# InvertingMixer.net
KiCad netlist of a schematic drawn in EAGLE
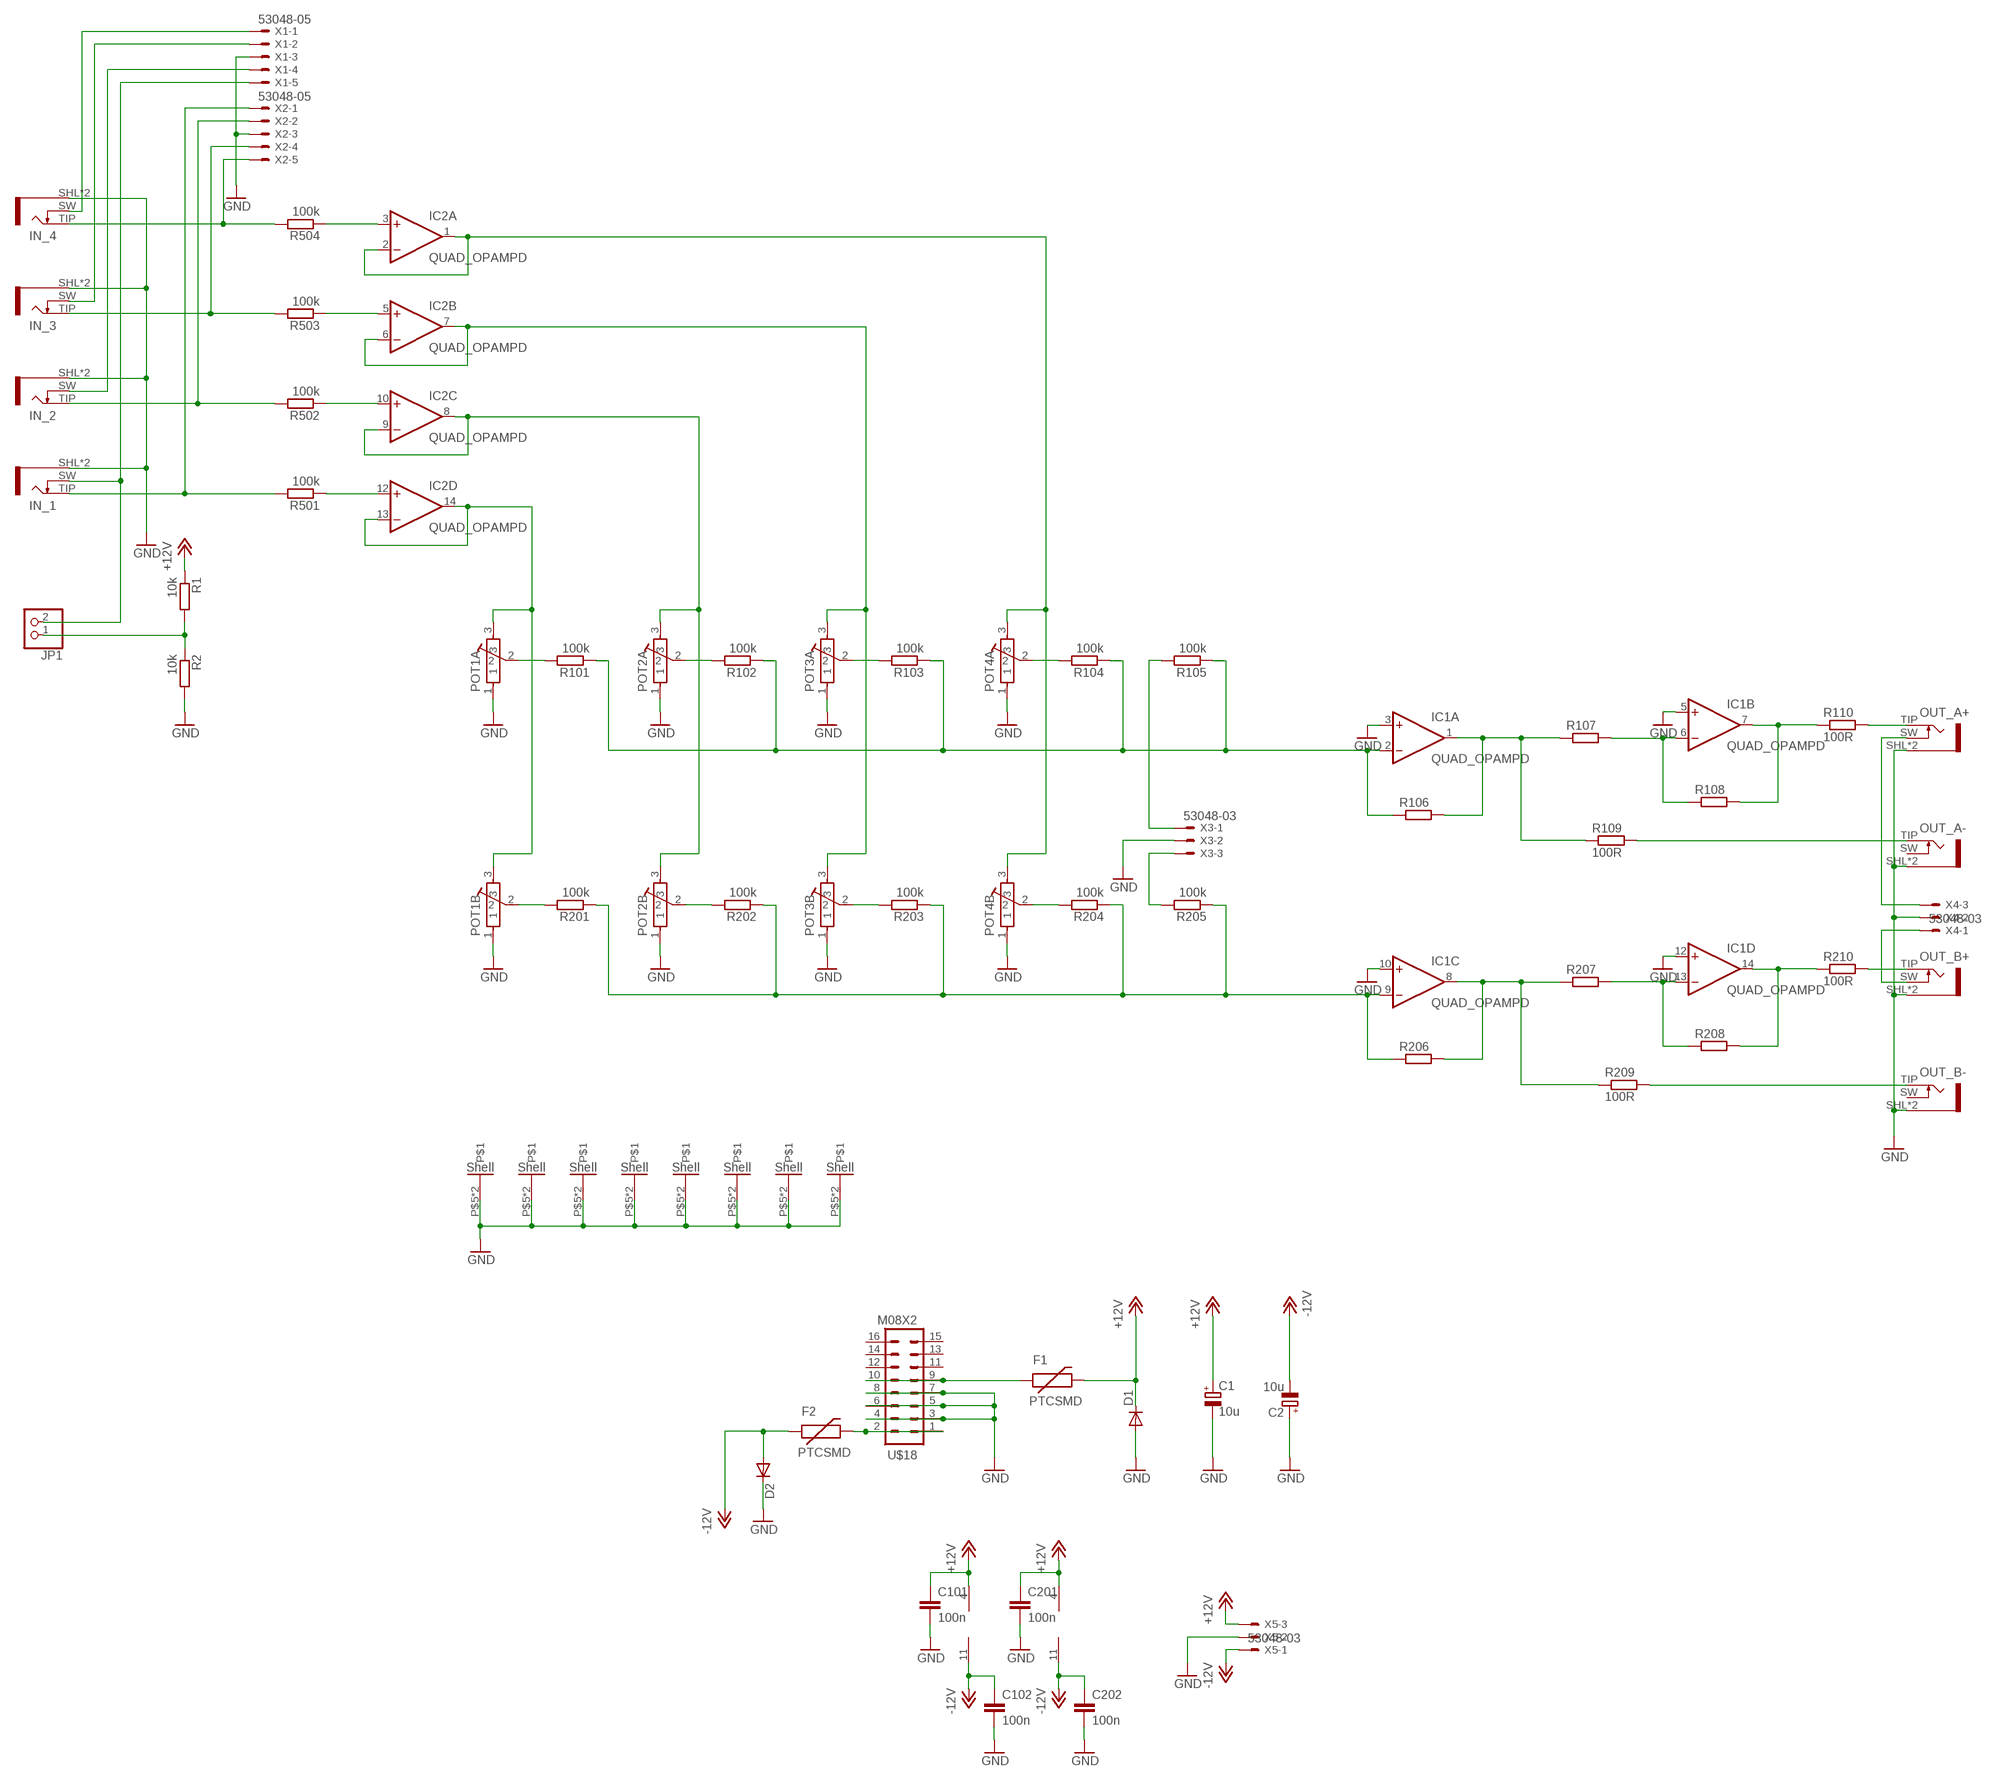
[diagram p0: schematic, sheet 1]

(export (version "E")
  (design (tool "Eeschema 10.0.6"))
  (components
    (comp (ref "C1")
      (value "10u")
      (footprint "eagle-import:PANASONIC_A")
      (libsource (lib "eagle-import") (part "CPOL-EUA"))
    )
    (comp (ref "C2")
      (value "10u")
      (footprint "eagle-import:PANASONIC_A")
      (libsource (lib "eagle-import") (part "CPOL-EUA"))
    )
    (comp (ref "C101")
      (value "100n")
      (footprint "eagle-import:C0603")
      (libsource (lib "eagle-import") (part "C-EUC0603"))
    )
    (comp (ref "C102")
      (value "100n")
      (footprint "eagle-import:C0603")
      (libsource (lib "eagle-import") (part "C-EUC0603"))
    )
    (comp (ref "C201")
      (value "100n")
      (footprint "eagle-import:C0603")
      (libsource (lib "eagle-import") (part "C-EUC0603"))
    )
    (comp (ref "C202")
      (value "100n")
      (footprint "eagle-import:C0603")
      (libsource (lib "eagle-import") (part "C-EUC0603"))
    )
    (comp (ref "D1")
      (value "DIODESMA")
      (footprint "eagle-import:SMA-DIODE")
      (libsource (lib "eagle-import") (part "DIODESMA"))
    )
    (comp (ref "D2")
      (value "DIODESMA")
      (footprint "eagle-import:SMA-DIODE")
      (libsource (lib "eagle-import") (part "DIODESMA"))
    )
    (comp (ref "F1")
      (value "PTCSMD")
      (footprint "eagle-import:PTC-1206")
      (libsource (lib "eagle-import") (part "PTCSMD"))
    )
    (comp (ref "F2")
      (value "PTCSMD")
      (footprint "eagle-import:PTC-1206")
      (libsource (lib "eagle-import") (part "PTCSMD"))
    )
    (comp (ref "IC1")
      (value "QUAD_OPAMPD")
      (footprint "eagle-import:SO14")
      (libsource (lib "eagle-import") (part "QUAD_OPAMPD"))
    )
    (comp (ref "IC2")
      (value "QUAD_OPAMPD")
      (footprint "eagle-import:SO14")
      (libsource (lib "eagle-import") (part "QUAD_OPAMPD"))
    )
    (comp (ref "IN_1")
      (value "JACK-PJ-301B")
      (footprint "eagle-import:PJ-301B")
      (libsource (lib "eagle-import") (part "JACK-PJ-301B"))
    )
    (comp (ref "IN_2")
      (value "JACK-PJ-301B")
      (footprint "eagle-import:PJ-301B")
      (libsource (lib "eagle-import") (part "JACK-PJ-301B"))
    )
    (comp (ref "IN_3")
      (value "JACK-PJ-301B")
      (footprint "eagle-import:PJ-301B")
      (libsource (lib "eagle-import") (part "JACK-PJ-301B"))
    )
    (comp (ref "IN_4")
      (value "JACK-PJ-301B")
      (footprint "eagle-import:PJ-301B")
      (libsource (lib "eagle-import") (part "JACK-PJ-301B"))
    )
    (comp (ref "JP1")
      (value "PINHD-1X2")
      (footprint "eagle-import:1X02")
      (libsource (lib "eagle-import") (part "PINHD-1X2"))
    )
    (comp (ref "OUT_A+")
      (value "JACK-PJ-301B")
      (footprint "eagle-import:PJ-301B")
      (libsource (lib "eagle-import") (part "JACK-PJ-301B"))
    )
    (comp (ref "OUT_A-")
      (value "JACK-PJ-301B")
      (footprint "eagle-import:PJ-301B")
      (libsource (lib "eagle-import") (part "JACK-PJ-301B"))
    )
    (comp (ref "OUT_B+")
      (value "JACK-PJ-301B")
      (footprint "eagle-import:PJ-301B")
      (libsource (lib "eagle-import") (part "JACK-PJ-301B"))
    )
    (comp (ref "OUT_B-")
      (value "JACK-PJ-301B")
      (footprint "eagle-import:PJ-301B")
      (libsource (lib "eagle-import") (part "JACK-PJ-301B"))
    )
    (comp (ref "POT1A")
      (value "POT-ALPS-RK09L1140")
      (footprint "eagle-import:POT-ALPS-RK09L1140")
      (libsource (lib "eagle-import") (part "POT-ALPS-RK09L1140"))
    )
    (comp (ref "POT1B")
      (value "POT-ALPS-RK09L1140")
      (footprint "eagle-import:POT-ALPS-RK09L1140")
      (libsource (lib "eagle-import") (part "POT-ALPS-RK09L1140"))
    )
    (comp (ref "POT2A")
      (value "POT-ALPS-RK09L1140")
      (footprint "eagle-import:POT-ALPS-RK09L1140")
      (libsource (lib "eagle-import") (part "POT-ALPS-RK09L1140"))
    )
    (comp (ref "POT2B")
      (value "POT-ALPS-RK09L1140")
      (footprint "eagle-import:POT-ALPS-RK09L1140")
      (libsource (lib "eagle-import") (part "POT-ALPS-RK09L1140"))
    )
    (comp (ref "POT3A")
      (value "POT-ALPS-RK09L1140")
      (footprint "eagle-import:POT-ALPS-RK09L1140")
      (libsource (lib "eagle-import") (part "POT-ALPS-RK09L1140"))
    )
    (comp (ref "POT3B")
      (value "POT-ALPS-RK09L1140")
      (footprint "eagle-import:POT-ALPS-RK09L1140")
      (libsource (lib "eagle-import") (part "POT-ALPS-RK09L1140"))
    )
    (comp (ref "POT4A")
      (value "POT-ALPS-RK09L1140")
      (footprint "eagle-import:POT-ALPS-RK09L1140")
      (libsource (lib "eagle-import") (part "POT-ALPS-RK09L1140"))
    )
    (comp (ref "POT4B")
      (value "POT-ALPS-RK09L1140")
      (footprint "eagle-import:POT-ALPS-RK09L1140")
      (libsource (lib "eagle-import") (part "POT-ALPS-RK09L1140"))
    )
    (comp (ref "R1")
      (value "10k")
      (footprint "eagle-import:R0603")
      (libsource (lib "eagle-import") (part "R-EU_R0603"))
    )
    (comp (ref "R2")
      (value "10k")
      (footprint "eagle-import:R0603")
      (libsource (lib "eagle-import") (part "R-EU_R0603"))
    )
    (comp (ref "R101")
      (value "100k")
      (footprint "eagle-import:R0603")
      (libsource (lib "eagle-import") (part "R-EU_R0603"))
    )
    (comp (ref "R102")
      (value "100k")
      (footprint "eagle-import:R0603")
      (libsource (lib "eagle-import") (part "R-EU_R0603"))
    )
    (comp (ref "R103")
      (value "100k")
      (footprint "eagle-import:R0603")
      (libsource (lib "eagle-import") (part "R-EU_R0603"))
    )
    (comp (ref "R104")
      (value "100k")
      (footprint "eagle-import:R0603")
      (libsource (lib "eagle-import") (part "R-EU_R0603"))
    )
    (comp (ref "R105")
      (value "100k")
      (footprint "eagle-import:R0603")
      (libsource (lib "eagle-import") (part "R-EU_R0603"))
    )
    (comp (ref "R106")
      (value "R-EU_R0603")
      (footprint "eagle-import:R0603")
      (libsource (lib "eagle-import") (part "R-EU_R0603"))
    )
    (comp (ref "R107")
      (value "R-EU_R0603")
      (footprint "eagle-import:R0603")
      (libsource (lib "eagle-import") (part "R-EU_R0603"))
    )
    (comp (ref "R108")
      (value "R-EU_R0603")
      (footprint "eagle-import:R0603")
      (libsource (lib "eagle-import") (part "R-EU_R0603"))
    )
    (comp (ref "R109")
      (value "100R")
      (footprint "eagle-import:R0603")
      (libsource (lib "eagle-import") (part "R-EU_R0603"))
    )
    (comp (ref "R110")
      (value "100R")
      (footprint "eagle-import:R0603")
      (libsource (lib "eagle-import") (part "R-EU_R0603"))
    )
    (comp (ref "R201")
      (value "100k")
      (footprint "eagle-import:R0603")
      (libsource (lib "eagle-import") (part "R-EU_R0603"))
    )
    (comp (ref "R202")
      (value "100k")
      (footprint "eagle-import:R0603")
      (libsource (lib "eagle-import") (part "R-EU_R0603"))
    )
    (comp (ref "R203")
      (value "100k")
      (footprint "eagle-import:R0603")
      (libsource (lib "eagle-import") (part "R-EU_R0603"))
    )
    (comp (ref "R204")
      (value "100k")
      (footprint "eagle-import:R0603")
      (libsource (lib "eagle-import") (part "R-EU_R0603"))
    )
    (comp (ref "R205")
      (value "100k")
      (footprint "eagle-import:R0603")
      (libsource (lib "eagle-import") (part "R-EU_R0603"))
    )
    (comp (ref "R206")
      (value "R-EU_R0603")
      (footprint "eagle-import:R0603")
      (libsource (lib "eagle-import") (part "R-EU_R0603"))
    )
    (comp (ref "R207")
      (value "R-EU_R0603")
      (footprint "eagle-import:R0603")
      (libsource (lib "eagle-import") (part "R-EU_R0603"))
    )
    (comp (ref "R208")
      (value "R-EU_R0603")
      (footprint "eagle-import:R0603")
      (libsource (lib "eagle-import") (part "R-EU_R0603"))
    )
    (comp (ref "R209")
      (value "100R")
      (footprint "eagle-import:R0603")
      (libsource (lib "eagle-import") (part "R-EU_R0603"))
    )
    (comp (ref "R210")
      (value "100R")
      (footprint "eagle-import:R0603")
      (libsource (lib "eagle-import") (part "R-EU_R0603"))
    )
    (comp (ref "R501")
      (value "100k")
      (footprint "eagle-import:R0603")
      (libsource (lib "eagle-import") (part "R-EU_R0603"))
    )
    (comp (ref "R502")
      (value "100k")
      (footprint "eagle-import:R0603")
      (libsource (lib "eagle-import") (part "R-EU_R0603"))
    )
    (comp (ref "R503")
      (value "100k")
      (footprint "eagle-import:R0603")
      (libsource (lib "eagle-import") (part "R-EU_R0603"))
    )
    (comp (ref "R504")
      (value "100k")
      (footprint "eagle-import:R0603")
      (libsource (lib "eagle-import") (part "R-EU_R0603"))
    )
    (comp (ref "U$18")
      (value "M08X2")
      (footprint "eagle-import:2X8")
      (libsource (lib "eagle-import") (part "M08X2"))
    )
    (comp (ref "X1")
      (value "53048-05")
      (footprint "eagle-import:53048-05")
      (fields (field (name "MF") "MOLEX") (field (name "MPN") "53048-0510"))
      (libsource (lib "eagle-import") (part "53?-05048"))
    )
    (comp (ref "X2")
      (value "53048-05")
      (footprint "eagle-import:53048-05")
      (fields (field (name "MF") "MOLEX") (field (name "MPN") "53048-0510"))
      (libsource (lib "eagle-import") (part "53?-05048"))
    )
    (comp (ref "X3")
      (value "53048-03")
      (footprint "eagle-import:53048-03")
      (fields (field (name "MF") "WALDOM/MOLEX") (field (name "MPN") "53048-0310"))
      (libsource (lib "eagle-import") (part "53?-03048"))
    )
    (comp (ref "X4")
      (value "53048-03")
      (footprint "eagle-import:53048-03")
      (fields (field (name "MF") "WALDOM/MOLEX") (field (name "MPN") "53048-0310"))
      (libsource (lib "eagle-import") (part "53?-03048"))
    )
    (comp (ref "X5")
      (value "53048-03")
      (footprint "eagle-import:53048-03")
      (fields (field (name "MF") "WALDOM/MOLEX") (field (name "MPN") "53048-0310"))
      (libsource (lib "eagle-import") (part "53?-03048"))
    )
  )
  (nets
    (net (code "1") (name "+12V") (class "Default")
      (node (ref "C1") (pin "+") (pinfunction "+_+") (pintype "passive"))
      (node (ref "C101") (pin "1") (pinfunction "1_1") (pintype "passive"))
      (node (ref "C201") (pin "1") (pinfunction "1_1") (pintype "passive"))
      (node (ref "D1") (pin "C") (pinfunction "C_C") (pintype "passive"))
      (node (ref "F1") (pin "2") (pinfunction "2_2") (pintype "bidirectional"))
      (node (ref "IC1") (pin "4") (pinfunction "V+_4") (pintype "power_in"))
      (node (ref "IC2") (pin "4") (pinfunction "V+_4") (pintype "power_in"))
      (node (ref "R1") (pin "1") (pinfunction "1_1") (pintype "passive"))
      (node (ref "X5") (pin "3") (pinfunction "S_3") (pintype "passive"))
    )
    (net (code "2") (name "-12V") (class "Default")
      (node (ref "C102") (pin "1") (pinfunction "1_1") (pintype "passive"))
      (node (ref "C2") (pin "-") (pinfunction "-_-") (pintype "passive"))
      (node (ref "C202") (pin "1") (pinfunction "1_1") (pintype "passive"))
      (node (ref "D2") (pin "A") (pinfunction "A_A") (pintype "passive"))
      (node (ref "F2") (pin "1") (pinfunction "1_1") (pintype "bidirectional"))
      (node (ref "IC1") (pin "11") (pinfunction "V-_11") (pintype "power_in"))
      (node (ref "IC2") (pin "11") (pinfunction "V-_11") (pintype "power_in"))
      (node (ref "X5") (pin "1") (pinfunction "S_1") (pintype "passive"))
    )
    (net (code "3") (name "GND") (class "Default")
      (node (ref "C1") (pin "-") (pinfunction "-_-") (pintype "passive"))
      (node (ref "C101") (pin "2") (pinfunction "2_2") (pintype "passive"))
      (node (ref "C102") (pin "2") (pinfunction "2_2") (pintype "passive"))
      (node (ref "C2") (pin "+") (pinfunction "+_+") (pintype "passive"))
      (node (ref "C201") (pin "2") (pinfunction "2_2") (pintype "passive"))
      (node (ref "C202") (pin "2") (pinfunction "2_2") (pintype "passive"))
      (node (ref "D1") (pin "A") (pinfunction "A_A") (pintype "passive"))
      (node (ref "D2") (pin "C") (pinfunction "C_C") (pintype "passive"))
      (node (ref "IC1") (pin "10") (pinfunction "+IN_10") (pintype "input"))
      (node (ref "IC1") (pin "12") (pinfunction "+IN_12") (pintype "input"))
      (node (ref "IC1") (pin "3") (pinfunction "+IN_3") (pintype "input"))
      (node (ref "IC1") (pin "5") (pinfunction "+IN_5") (pintype "input"))
      (node (ref "IN_1") (pin "SHL") (pinfunction "SLEEVE_SHL") (pintype "passive"))
      (node (ref "IN_1") (pin "SLV") (pinfunction "SLEEVE_SLV") (pintype "passive"))
      (node (ref "IN_2") (pin "SHL") (pinfunction "SLEEVE_SHL") (pintype "passive"))
      (node (ref "IN_2") (pin "SLV") (pinfunction "SLEEVE_SLV") (pintype "passive"))
      (node (ref "IN_3") (pin "SHL") (pinfunction "SLEEVE_SHL") (pintype "passive"))
      (node (ref "IN_3") (pin "SLV") (pinfunction "SLEEVE_SLV") (pintype "passive"))
      (node (ref "IN_4") (pin "SHL") (pinfunction "SLEEVE_SHL") (pintype "passive"))
      (node (ref "IN_4") (pin "SLV") (pinfunction "SLEEVE_SLV") (pintype "passive"))
      (node (ref "OUT_A+") (pin "SHL") (pinfunction "SLEEVE_SHL") (pintype "passive"))
      (node (ref "OUT_A+") (pin "SLV") (pinfunction "SLEEVE_SLV") (pintype "passive"))
      (node (ref "OUT_A-") (pin "SHL") (pinfunction "SLEEVE_SHL") (pintype "passive"))
      (node (ref "OUT_A-") (pin "SLV") (pinfunction "SLEEVE_SLV") (pintype "passive"))
      (node (ref "OUT_B+") (pin "SHL") (pinfunction "SLEEVE_SHL") (pintype "passive"))
      (node (ref "OUT_B+") (pin "SLV") (pinfunction "SLEEVE_SLV") (pintype "passive"))
      (node (ref "OUT_B-") (pin "SHL") (pinfunction "SLEEVE_SHL") (pintype "passive"))
      (node (ref "OUT_B-") (pin "SLV") (pinfunction "SLEEVE_SLV") (pintype "passive"))
      (node (ref "POT1A") (pin "1") (pinfunction "1_1") (pintype "bidirectional"))
      (node (ref "POT1A") (pin "P$5") (pinfunction "P$1_P$5") (pintype "bidirectional"))
      (node (ref "POT1A") (pin "P$6") (pinfunction "P$1_P$6") (pintype "bidirectional"))
      (node (ref "POT1B") (pin "1") (pinfunction "1_1") (pintype "bidirectional"))
      (node (ref "POT1B") (pin "P$5") (pinfunction "P$1_P$5") (pintype "bidirectional"))
      (node (ref "POT1B") (pin "P$6") (pinfunction "P$1_P$6") (pintype "bidirectional"))
      (node (ref "POT2A") (pin "1") (pinfunction "1_1") (pintype "bidirectional"))
      (node (ref "POT2A") (pin "P$5") (pinfunction "P$1_P$5") (pintype "bidirectional"))
      (node (ref "POT2A") (pin "P$6") (pinfunction "P$1_P$6") (pintype "bidirectional"))
      (node (ref "POT2B") (pin "1") (pinfunction "1_1") (pintype "bidirectional"))
      (node (ref "POT2B") (pin "P$5") (pinfunction "P$1_P$5") (pintype "bidirectional"))
      (node (ref "POT2B") (pin "P$6") (pinfunction "P$1_P$6") (pintype "bidirectional"))
      (node (ref "POT3A") (pin "1") (pinfunction "1_1") (pintype "bidirectional"))
      (node (ref "POT3A") (pin "P$5") (pinfunction "P$1_P$5") (pintype "bidirectional"))
      (node (ref "POT3A") (pin "P$6") (pinfunction "P$1_P$6") (pintype "bidirectional"))
      (node (ref "POT3B") (pin "1") (pinfunction "1_1") (pintype "bidirectional"))
      (node (ref "POT3B") (pin "P$5") (pinfunction "P$1_P$5") (pintype "bidirectional"))
      (node (ref "POT3B") (pin "P$6") (pinfunction "P$1_P$6") (pintype "bidirectional"))
      (node (ref "POT4A") (pin "1") (pinfunction "1_1") (pintype "bidirectional"))
      (node (ref "POT4A") (pin "P$5") (pinfunction "P$1_P$5") (pintype "bidirectional"))
      (node (ref "POT4A") (pin "P$6") (pinfunction "P$1_P$6") (pintype "bidirectional"))
      (node (ref "POT4B") (pin "1") (pinfunction "1_1") (pintype "bidirectional"))
      (node (ref "POT4B") (pin "P$5") (pinfunction "P$1_P$5") (pintype "bidirectional"))
      (node (ref "POT4B") (pin "P$6") (pinfunction "P$1_P$6") (pintype "bidirectional"))
      (node (ref "R2") (pin "2") (pinfunction "2_2") (pintype "passive"))
      (node (ref "U$18") (pin "3") (pinfunction "3_3") (pintype "passive"))
      (node (ref "U$18") (pin "4") (pinfunction "4_4") (pintype "passive"))
      (node (ref "U$18") (pin "5") (pinfunction "5_5") (pintype "passive"))
      (node (ref "U$18") (pin "6") (pinfunction "6_6") (pintype "passive"))
      (node (ref "U$18") (pin "7") (pinfunction "7_7") (pintype "passive"))
      (node (ref "U$18") (pin "8") (pinfunction "8_8") (pintype "passive"))
      (node (ref "X1") (pin "3") (pinfunction "S_3") (pintype "passive"))
      (node (ref "X2") (pin "3") (pinfunction "S_3") (pintype "passive"))
      (node (ref "X3") (pin "2") (pinfunction "S_2") (pintype "passive"))
      (node (ref "X4") (pin "2") (pinfunction "S_2") (pintype "passive"))
      (node (ref "X5") (pin "2") (pinfunction "S_2") (pintype "passive"))
    )
    (net (code "4") (name "Net-(F1-Pad1)") (class "Default")
      (node (ref "F1") (pin "1") (pinfunction "1_1") (pintype "bidirectional"))
      (node (ref "U$18") (pin "10") (pinfunction "10_10") (pintype "passive"))
      (node (ref "U$18") (pin "9") (pinfunction "9_9") (pintype "passive"))
    )
    (net (code "5") (name "Net-(F2-Pad2)") (class "Default")
      (node (ref "F2") (pin "2") (pinfunction "2_2") (pintype "bidirectional"))
      (node (ref "U$18") (pin "1") (pinfunction "1_1") (pintype "passive"))
      (node (ref "U$18") (pin "2") (pinfunction "2_2") (pintype "passive"))
    )
    (net (code "6") (name "Net-(IC1A--IN)") (class "Default")
      (node (ref "IC1") (pin "2") (pinfunction "-IN_2") (pintype "input"))
      (node (ref "R101") (pin "1") (pinfunction "1_1") (pintype "passive"))
      (node (ref "R102") (pin "1") (pinfunction "1_1") (pintype "passive"))
      (node (ref "R103") (pin "1") (pinfunction "1_1") (pintype "passive"))
      (node (ref "R104") (pin "1") (pinfunction "1_1") (pintype "passive"))
      (node (ref "R105") (pin "1") (pinfunction "1_1") (pintype "passive"))
      (node (ref "R106") (pin "1") (pinfunction "1_1") (pintype "passive"))
    )
    (net (code "7") (name "Net-(IC1A-OUT)") (class "Default")
      (node (ref "IC1") (pin "1") (pinfunction "OUT_1") (pintype "output"))
      (node (ref "R106") (pin "2") (pinfunction "2_2") (pintype "passive"))
      (node (ref "R107") (pin "1") (pinfunction "1_1") (pintype "passive"))
      (node (ref "R109") (pin "1") (pinfunction "1_1") (pintype "passive"))
    )
    (net (code "8") (name "Net-(IC1B--IN)") (class "Default")
      (node (ref "IC1") (pin "6") (pinfunction "-IN_6") (pintype "input"))
      (node (ref "R107") (pin "2") (pinfunction "2_2") (pintype "passive"))
      (node (ref "R108") (pin "1") (pinfunction "1_1") (pintype "passive"))
    )
    (net (code "9") (name "Net-(IC1B-OUT)") (class "Default")
      (node (ref "IC1") (pin "7") (pinfunction "OUT_7") (pintype "output"))
      (node (ref "R108") (pin "2") (pinfunction "2_2") (pintype "passive"))
      (node (ref "R110") (pin "1") (pinfunction "1_1") (pintype "passive"))
    )
    (net (code "10") (name "Net-(IC1C--IN)") (class "Default")
      (node (ref "IC1") (pin "9") (pinfunction "-IN_9") (pintype "input"))
      (node (ref "R201") (pin "1") (pinfunction "1_1") (pintype "passive"))
      (node (ref "R202") (pin "1") (pinfunction "1_1") (pintype "passive"))
      (node (ref "R203") (pin "1") (pinfunction "1_1") (pintype "passive"))
      (node (ref "R204") (pin "1") (pinfunction "1_1") (pintype "passive"))
      (node (ref "R205") (pin "1") (pinfunction "1_1") (pintype "passive"))
      (node (ref "R206") (pin "1") (pinfunction "1_1") (pintype "passive"))
    )
    (net (code "11") (name "Net-(IC1C-OUT)") (class "Default")
      (node (ref "IC1") (pin "8") (pinfunction "OUT_8") (pintype "output"))
      (node (ref "R206") (pin "2") (pinfunction "2_2") (pintype "passive"))
      (node (ref "R207") (pin "1") (pinfunction "1_1") (pintype "passive"))
      (node (ref "R209") (pin "1") (pinfunction "1_1") (pintype "passive"))
    )
    (net (code "12") (name "Net-(IC1D--IN)") (class "Default")
      (node (ref "IC1") (pin "13") (pinfunction "-IN_13") (pintype "input"))
      (node (ref "R207") (pin "2") (pinfunction "2_2") (pintype "passive"))
      (node (ref "R208") (pin "1") (pinfunction "1_1") (pintype "passive"))
    )
    (net (code "13") (name "Net-(IC1D-OUT)") (class "Default")
      (node (ref "IC1") (pin "14") (pinfunction "OUT_14") (pintype "output"))
      (node (ref "R208") (pin "2") (pinfunction "2_2") (pintype "passive"))
      (node (ref "R210") (pin "1") (pinfunction "1_1") (pintype "passive"))
    )
    (net (code "14") (name "Net-(IC2A-+IN)") (class "Default")
      (node (ref "IC2") (pin "3") (pinfunction "+IN_3") (pintype "input"))
      (node (ref "R504") (pin "1") (pinfunction "1_1") (pintype "passive"))
    )
    (net (code "15") (name "Net-(IC2A--IN)") (class "Default")
      (node (ref "IC2") (pin "1") (pinfunction "OUT_1") (pintype "output"))
      (node (ref "IC2") (pin "2") (pinfunction "-IN_2") (pintype "input"))
      (node (ref "POT4A") (pin "3") (pinfunction "3_3") (pintype "bidirectional"))
      (node (ref "POT4B") (pin "3") (pinfunction "3_3") (pintype "bidirectional"))
    )
    (net (code "16") (name "Net-(IC2B-+IN)") (class "Default")
      (node (ref "IC2") (pin "5") (pinfunction "+IN_5") (pintype "input"))
      (node (ref "R503") (pin "1") (pinfunction "1_1") (pintype "passive"))
    )
    (net (code "17") (name "Net-(IC2B--IN)") (class "Default")
      (node (ref "IC2") (pin "6") (pinfunction "-IN_6") (pintype "input"))
      (node (ref "IC2") (pin "7") (pinfunction "OUT_7") (pintype "output"))
      (node (ref "POT3A") (pin "3") (pinfunction "3_3") (pintype "bidirectional"))
      (node (ref "POT3B") (pin "3") (pinfunction "3_3") (pintype "bidirectional"))
    )
    (net (code "18") (name "Net-(IC2C-+IN)") (class "Default")
      (node (ref "IC2") (pin "10") (pinfunction "+IN_10") (pintype "input"))
      (node (ref "R502") (pin "1") (pinfunction "1_1") (pintype "passive"))
    )
    (net (code "19") (name "Net-(IC2C--IN)") (class "Default")
      (node (ref "IC2") (pin "8") (pinfunction "OUT_8") (pintype "output"))
      (node (ref "IC2") (pin "9") (pinfunction "-IN_9") (pintype "input"))
      (node (ref "POT2A") (pin "3") (pinfunction "3_3") (pintype "bidirectional"))
      (node (ref "POT2B") (pin "3") (pinfunction "3_3") (pintype "bidirectional"))
    )
    (net (code "20") (name "Net-(IC2D-+IN)") (class "Default")
      (node (ref "IC2") (pin "12") (pinfunction "+IN_12") (pintype "input"))
      (node (ref "R501") (pin "1") (pinfunction "1_1") (pintype "passive"))
    )
    (net (code "21") (name "Net-(IC2D--IN)") (class "Default")
      (node (ref "IC2") (pin "13") (pinfunction "-IN_13") (pintype "input"))
      (node (ref "IC2") (pin "14") (pinfunction "OUT_14") (pintype "output"))
      (node (ref "POT1A") (pin "3") (pinfunction "3_3") (pintype "bidirectional"))
      (node (ref "POT1B") (pin "3") (pinfunction "3_3") (pintype "bidirectional"))
    )
    (net (code "22") (name "Net-(JP1-Pad1)") (class "Default")
      (node (ref "JP1") (pin "1") (pinfunction "1_1") (pintype "passive"))
      (node (ref "R1") (pin "2") (pinfunction "2_2") (pintype "passive"))
      (node (ref "R2") (pin "1") (pinfunction "1_1") (pintype "passive"))
    )
    (net (code "23") (name "Net-(OUT_A+-PadTIP)") (class "Default")
      (node (ref "OUT_A+") (pin "TIP") (pinfunction "TIP_TIP") (pintype "passive"))
      (node (ref "R110") (pin "2") (pinfunction "2_2") (pintype "passive"))
    )
    (net (code "24") (name "Net-(OUT_A--PadTIP)") (class "Default")
      (node (ref "OUT_A-") (pin "TIP") (pinfunction "TIP_TIP") (pintype "passive"))
      (node (ref "R109") (pin "2") (pinfunction "2_2") (pintype "passive"))
    )
    (net (code "25") (name "Net-(OUT_B+-PadTIP)") (class "Default")
      (node (ref "OUT_B+") (pin "TIP") (pinfunction "TIP_TIP") (pintype "passive"))
      (node (ref "R210") (pin "2") (pinfunction "2_2") (pintype "passive"))
    )
    (net (code "26") (name "Net-(OUT_B--PadTIP)") (class "Default")
      (node (ref "OUT_B-") (pin "TIP") (pinfunction "TIP_TIP") (pintype "passive"))
      (node (ref "R209") (pin "2") (pinfunction "2_2") (pintype "passive"))
    )
    (net (code "27") (name "Net-(POT1A-Pad2)") (class "Default")
      (node (ref "POT1A") (pin "2") (pinfunction "2_2") (pintype "bidirectional"))
      (node (ref "R101") (pin "2") (pinfunction "2_2") (pintype "passive"))
    )
    (net (code "28") (name "Net-(POT1B-Pad2)") (class "Default")
      (node (ref "POT1B") (pin "2") (pinfunction "2_2") (pintype "bidirectional"))
      (node (ref "R201") (pin "2") (pinfunction "2_2") (pintype "passive"))
    )
    (net (code "29") (name "Net-(POT2A-Pad2)") (class "Default")
      (node (ref "POT2A") (pin "2") (pinfunction "2_2") (pintype "bidirectional"))
      (node (ref "R102") (pin "2") (pinfunction "2_2") (pintype "passive"))
    )
    (net (code "30") (name "Net-(POT2B-Pad2)") (class "Default")
      (node (ref "POT2B") (pin "2") (pinfunction "2_2") (pintype "bidirectional"))
      (node (ref "R202") (pin "2") (pinfunction "2_2") (pintype "passive"))
    )
    (net (code "31") (name "Net-(POT3A-Pad2)") (class "Default")
      (node (ref "POT3A") (pin "2") (pinfunction "2_2") (pintype "bidirectional"))
      (node (ref "R103") (pin "2") (pinfunction "2_2") (pintype "passive"))
    )
    (net (code "32") (name "Net-(POT3B-Pad2)") (class "Default")
      (node (ref "POT3B") (pin "2") (pinfunction "2_2") (pintype "bidirectional"))
      (node (ref "R203") (pin "2") (pinfunction "2_2") (pintype "passive"))
    )
    (net (code "33") (name "Net-(POT4A-Pad2)") (class "Default")
      (node (ref "POT4A") (pin "2") (pinfunction "2_2") (pintype "bidirectional"))
      (node (ref "R104") (pin "2") (pinfunction "2_2") (pintype "passive"))
    )
    (net (code "34") (name "Net-(POT4B-Pad2)") (class "Default")
      (node (ref "POT4B") (pin "2") (pinfunction "2_2") (pintype "bidirectional"))
      (node (ref "R204") (pin "2") (pinfunction "2_2") (pintype "passive"))
    )
    (net (code "35") (name "Net-(X1A-S)") (class "Default")
      (node (ref "IN_4") (pin "SW") (pinfunction "SW_SW") (pintype "passive"))
      (node (ref "X1") (pin "1") (pinfunction "S_1") (pintype "passive"))
    )
    (net (code "36") (name "Net-(X1B-S)") (class "Default")
      (node (ref "IN_3") (pin "SW") (pinfunction "SW_SW") (pintype "passive"))
      (node (ref "X1") (pin "2") (pinfunction "S_2") (pintype "passive"))
    )
    (net (code "37") (name "Net-(X1D-S)") (class "Default")
      (node (ref "IN_2") (pin "SW") (pinfunction "SW_SW") (pintype "passive"))
      (node (ref "X1") (pin "4") (pinfunction "S_4") (pintype "passive"))
    )
    (net (code "38") (name "Net-(X1E-S)") (class "Default")
      (node (ref "IN_1") (pin "SW") (pinfunction "SW_SW") (pintype "passive"))
      (node (ref "JP1") (pin "2") (pinfunction "2_2") (pintype "passive"))
      (node (ref "X1") (pin "5") (pinfunction "S_5") (pintype "passive"))
    )
    (net (code "39") (name "Net-(X2A-S)") (class "Default")
      (node (ref "IN_1") (pin "TIP") (pinfunction "TIP_TIP") (pintype "passive"))
      (node (ref "R501") (pin "2") (pinfunction "2_2") (pintype "passive"))
      (node (ref "X2") (pin "1") (pinfunction "S_1") (pintype "passive"))
    )
    (net (code "40") (name "Net-(X2B-S)") (class "Default")
      (node (ref "IN_2") (pin "TIP") (pinfunction "TIP_TIP") (pintype "passive"))
      (node (ref "R502") (pin "2") (pinfunction "2_2") (pintype "passive"))
      (node (ref "X2") (pin "2") (pinfunction "S_2") (pintype "passive"))
    )
    (net (code "41") (name "Net-(X2D-S)") (class "Default")
      (node (ref "IN_3") (pin "TIP") (pinfunction "TIP_TIP") (pintype "passive"))
      (node (ref "R503") (pin "2") (pinfunction "2_2") (pintype "passive"))
      (node (ref "X2") (pin "4") (pinfunction "S_4") (pintype "passive"))
    )
    (net (code "42") (name "Net-(X2E-S)") (class "Default")
      (node (ref "IN_4") (pin "TIP") (pinfunction "TIP_TIP") (pintype "passive"))
      (node (ref "R504") (pin "2") (pinfunction "2_2") (pintype "passive"))
      (node (ref "X2") (pin "5") (pinfunction "S_5") (pintype "passive"))
    )
    (net (code "43") (name "Net-(X3A-S)") (class "Default")
      (node (ref "R105") (pin "2") (pinfunction "2_2") (pintype "passive"))
      (node (ref "X3") (pin "1") (pinfunction "S_1") (pintype "passive"))
    )
    (net (code "44") (name "Net-(X3C-S)") (class "Default")
      (node (ref "R205") (pin "2") (pinfunction "2_2") (pintype "passive"))
      (node (ref "X3") (pin "3") (pinfunction "S_3") (pintype "passive"))
    )
    (net (code "45") (name "Net-(X4A-S)") (class "Default")
      (node (ref "OUT_B+") (pin "SW") (pinfunction "SW_SW") (pintype "passive"))
      (node (ref "X4") (pin "1") (pinfunction "S_1") (pintype "passive"))
    )
    (net (code "46") (name "Net-(X4C-S)") (class "Default")
      (node (ref "OUT_A+") (pin "SW") (pinfunction "SW_SW") (pintype "passive"))
      (node (ref "X4") (pin "3") (pinfunction "S_3") (pintype "passive"))
    )
    (net (code "47") (name "unconnected-(OUT_A--PadSW)") (class "Default")
      (node (ref "OUT_A-") (pin "SW") (pinfunction "SW_SW") (pintype "passive"))
    )
    (net (code "48") (name "unconnected-(OUT_B--PadSW)") (class "Default")
      (node (ref "OUT_B-") (pin "SW") (pinfunction "SW_SW") (pintype "passive"))
    )
    (net (code "49") (name "unconnected-(U$18-Pad11)") (class "Default")
      (node (ref "U$18") (pin "11") (pinfunction "11_11") (pintype "passive"))
    )
    (net (code "50") (name "unconnected-(U$18-Pad12)") (class "Default")
      (node (ref "U$18") (pin "12") (pinfunction "12_12") (pintype "passive"))
    )
    (net (code "51") (name "unconnected-(U$18-Pad13)") (class "Default")
      (node (ref "U$18") (pin "13") (pinfunction "13_13") (pintype "passive"))
    )
    (net (code "52") (name "unconnected-(U$18-Pad14)") (class "Default")
      (node (ref "U$18") (pin "14") (pinfunction "14_14") (pintype "passive"))
    )
    (net (code "53") (name "unconnected-(U$18-Pad15)") (class "Default")
      (node (ref "U$18") (pin "15") (pinfunction "15_15") (pintype "passive"))
    )
    (net (code "54") (name "unconnected-(U$18-Pad16)") (class "Default")
      (node (ref "U$18") (pin "16") (pinfunction "16_16") (pintype "passive"))
    )
  )
)
